# D1_Breakout_-_LCD_SMD_Dupont_RJ45_Logo.net
KiCad netlist of a schematic drawn in EAGLE
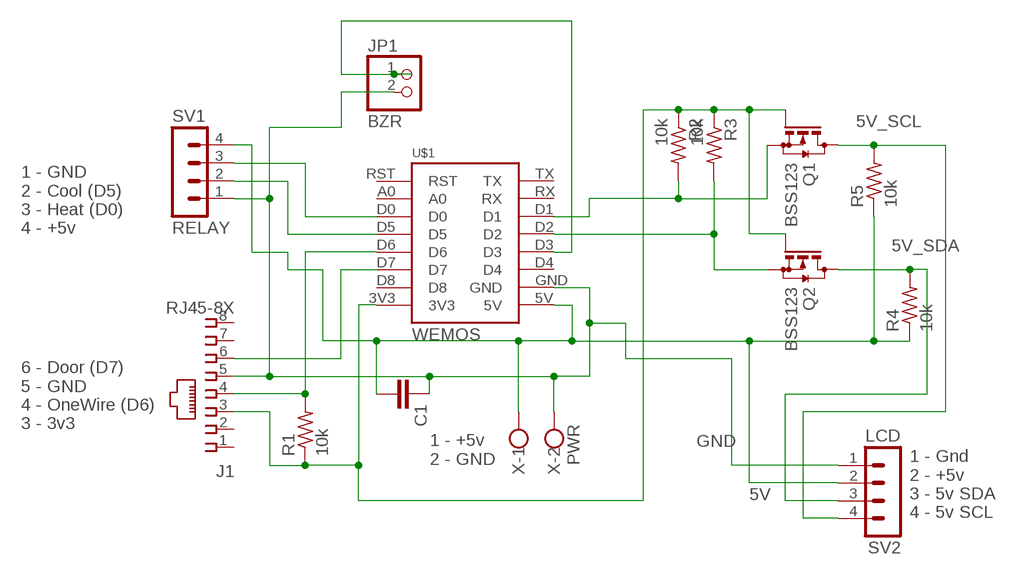
[diagram p0: schematic, sheet 1]

(export (version "E")
  (design (tool "Eeschema 10.0.6"))
  (components
    (comp (ref "C1")
      (value "C-EUC1206")
      (footprint "eagle-import:C1206")
      (libsource (lib "eagle-import") (part "C-EUC1206"))
    )
    (comp (ref "J1")
      (value "RJ45-8X")
      (footprint "eagle-import:RJ45-NO-SHIELD-NOLINE")
      (libsource (lib "eagle-import") (part "RJ45-8X"))
    )
    (comp (ref "JP1")
      (value "BZR")
      (footprint "eagle-import:1X02")
      (libsource (lib "eagle-import") (part "PINHD-1X2"))
    )
    (comp (ref "Q1")
      (value "BSS123")
      (footprint "eagle-import:SOT23")
      (libsource (lib "eagle-import") (part "BSS123"))
    )
    (comp (ref "Q2")
      (value "BSS123")
      (footprint "eagle-import:SOT23")
      (libsource (lib "eagle-import") (part "BSS123"))
    )
    (comp (ref "R1")
      (value "10k")
      (footprint "eagle-import:R0805")
      (libsource (lib "eagle-import") (part "R-US_R0805"))
    )
    (comp (ref "R2")
      (value "10k")
      (footprint "eagle-import:R0805")
      (libsource (lib "eagle-import") (part "R-US_R0805"))
    )
    (comp (ref "R3")
      (value "10k")
      (footprint "eagle-import:R0805")
      (libsource (lib "eagle-import") (part "R-US_R0805"))
    )
    (comp (ref "R4")
      (value "10k")
      (footprint "eagle-import:R0805")
      (libsource (lib "eagle-import") (part "R-US_R0805"))
    )
    (comp (ref "R5")
      (value "10k")
      (footprint "eagle-import:R0805")
      (libsource (lib "eagle-import") (part "R-US_R0805"))
    )
    (comp (ref "SV1")
      (value "RELAY")
      (footprint "eagle-import:MA04-1")
      (libsource (lib "eagle-import") (part "MA04-1"))
    )
    (comp (ref "SV2")
      (value "LCD")
      (footprint "eagle-import:MA04-1")
      (libsource (lib "eagle-import") (part "MA04-1"))
    )
    (comp (ref "U$1")
      (value "WEMOS")
      (footprint "eagle-import:WEMOS")
      (libsource (lib "eagle-import") (part "WEMOS"))
    )
    (comp (ref "X")
      (value "PWR")
      (footprint "eagle-import:W237-102")
      (fields (field (name "MPN") "237-102"))
      (libsource (lib "eagle-import") (part "W237-102"))
    )
  )
  (nets
    (net (code "1") (name "/5V") (class "Default")
      (node (ref "C1") (pin "2") (pinfunction "2_2") (pintype "passive"))
      (node (ref "R4") (pin "1") (pinfunction "1_1") (pintype "passive"))
      (node (ref "R5") (pin "1") (pinfunction "1_1") (pintype "passive"))
      (node (ref "SV1") (pin "4") (pinfunction "4_4") (pintype "passive"))
      (node (ref "SV2") (pin "2") (pinfunction "2_2") (pintype "passive"))
      (node (ref "U$1") (pin "5V") (pinfunction "5V_5V") (pintype "bidirectional"))
      (node (ref "X") (pin "1") (pinfunction "KL_1") (pintype "passive"))
    )
    (net (code "2") (name "/5V_SCL") (class "Default")
      (node (ref "Q1") (pin "3") (pinfunction "D_3") (pintype "passive"))
      (node (ref "R5") (pin "2") (pinfunction "2_2") (pintype "passive"))
      (node (ref "SV2") (pin "4") (pinfunction "4_4") (pintype "passive"))
    )
    (net (code "3") (name "/5V_SDA") (class "Default")
      (node (ref "Q2") (pin "3") (pinfunction "D_3") (pintype "passive"))
      (node (ref "R4") (pin "2") (pinfunction "2_2") (pintype "passive"))
      (node (ref "SV2") (pin "3") (pinfunction "3_3") (pintype "passive"))
    )
    (net (code "4") (name "/GND") (class "Default")
      (node (ref "C1") (pin "1") (pinfunction "1_1") (pintype "passive"))
      (node (ref "J1") (pin "5") (pinfunction "5_5") (pintype "passive"))
      (node (ref "JP1") (pin "2") (pinfunction "2_2") (pintype "passive"))
      (node (ref "SV1") (pin "1") (pinfunction "1_1") (pintype "passive"))
      (node (ref "SV2") (pin "1") (pinfunction "1_1") (pintype "passive"))
      (node (ref "U$1") (pin "GND") (pinfunction "GND_GND") (pintype "bidirectional"))
      (node (ref "X") (pin "2") (pinfunction "KL_2") (pintype "passive"))
    )
    (net (code "5") (name "Net-(J1-Pad4)") (class "Default")
      (node (ref "J1") (pin "4") (pinfunction "4_4") (pintype "passive"))
      (node (ref "R1") (pin "2") (pinfunction "2_2") (pintype "passive"))
      (node (ref "U$1") (pin "D6") (pinfunction "D6_D6") (pintype "bidirectional"))
    )
    (net (code "6") (name "Net-(J1-Pad6)") (class "Default")
      (node (ref "J1") (pin "6") (pinfunction "6_6") (pintype "passive"))
      (node (ref "U$1") (pin "D7") (pinfunction "D7_D7") (pintype "bidirectional"))
    )
    (net (code "7") (name "Net-(JP1-Pad1)") (class "Default")
      (node (ref "JP1") (pin "1") (pinfunction "1_1") (pintype "passive"))
      (node (ref "U$1") (pin "D3") (pinfunction "D3_D3") (pintype "bidirectional"))
    )
    (net (code "8") (name "Net-(Q1-G)") (class "Default")
      (node (ref "J1") (pin "3") (pinfunction "3_3") (pintype "passive"))
      (node (ref "Q1") (pin "1") (pinfunction "G_1") (pintype "passive"))
      (node (ref "Q2") (pin "1") (pinfunction "G_1") (pintype "passive"))
      (node (ref "R1") (pin "1") (pinfunction "1_1") (pintype "passive"))
      (node (ref "R2") (pin "1") (pinfunction "1_1") (pintype "passive"))
      (node (ref "R3") (pin "1") (pinfunction "1_1") (pintype "passive"))
      (node (ref "U$1") (pin "3V3") (pinfunction "3V3_3V3") (pintype "bidirectional"))
    )
    (net (code "9") (name "Net-(Q1-S)") (class "Default")
      (node (ref "Q1") (pin "2") (pinfunction "S_2") (pintype "passive"))
      (node (ref "R2") (pin "2") (pinfunction "2_2") (pintype "passive"))
      (node (ref "U$1") (pin "D1") (pinfunction "D1_D1") (pintype "bidirectional"))
    )
    (net (code "10") (name "Net-(Q2-S)") (class "Default")
      (node (ref "Q2") (pin "2") (pinfunction "S_2") (pintype "passive"))
      (node (ref "R3") (pin "2") (pinfunction "2_2") (pintype "passive"))
      (node (ref "U$1") (pin "D2") (pinfunction "D2_D2") (pintype "bidirectional"))
    )
    (net (code "11") (name "Net-(SV1-Pad2)") (class "Default")
      (node (ref "SV1") (pin "2") (pinfunction "2_2") (pintype "passive"))
      (node (ref "U$1") (pin "D5") (pinfunction "D5_D5") (pintype "bidirectional"))
    )
    (net (code "12") (name "Net-(SV1-Pad3)") (class "Default")
      (node (ref "SV1") (pin "3") (pinfunction "3_3") (pintype "passive"))
      (node (ref "U$1") (pin "D0") (pinfunction "D0_D0") (pintype "bidirectional"))
    )
    (net (code "13") (name "unconnected-(J1-Pad1)") (class "Default")
      (node (ref "J1") (pin "1") (pinfunction "1_1") (pintype "passive"))
    )
    (net (code "14") (name "unconnected-(J1-Pad2)") (class "Default")
      (node (ref "J1") (pin "2") (pinfunction "2_2") (pintype "passive"))
    )
    (net (code "15") (name "unconnected-(J1-Pad7)") (class "Default")
      (node (ref "J1") (pin "7") (pinfunction "7_7") (pintype "passive"))
    )
    (net (code "16") (name "unconnected-(J1-Pad8)") (class "Default")
      (node (ref "J1") (pin "8") (pinfunction "8_8") (pintype "passive"))
    )
    (net (code "17") (name "unconnected-(U$1-PadA0)") (class "Default")
      (node (ref "U$1") (pin "A0") (pinfunction "A0_A0") (pintype "bidirectional"))
    )
    (net (code "18") (name "unconnected-(U$1-PadD4)") (class "Default")
      (node (ref "U$1") (pin "D4") (pinfunction "D4_D4") (pintype "bidirectional"))
    )
    (net (code "19") (name "unconnected-(U$1-PadD8)") (class "Default")
      (node (ref "U$1") (pin "D8") (pinfunction "D8_D8") (pintype "bidirectional"))
    )
    (net (code "20") (name "unconnected-(U$1-PadRST)") (class "Default")
      (node (ref "U$1") (pin "RST") (pinfunction "RST_RST") (pintype "bidirectional"))
    )
    (net (code "21") (name "unconnected-(U$1-PadRX)") (class "Default")
      (node (ref "U$1") (pin "RX") (pinfunction "RX_RX") (pintype "bidirectional"))
    )
    (net (code "22") (name "unconnected-(U$1-PadTX)") (class "Default")
      (node (ref "U$1") (pin "TX") (pinfunction "TX_TX") (pintype "bidirectional"))
    )
  )
)
